# Main.net
KiCad netlist of a schematic drawn in EAGLE
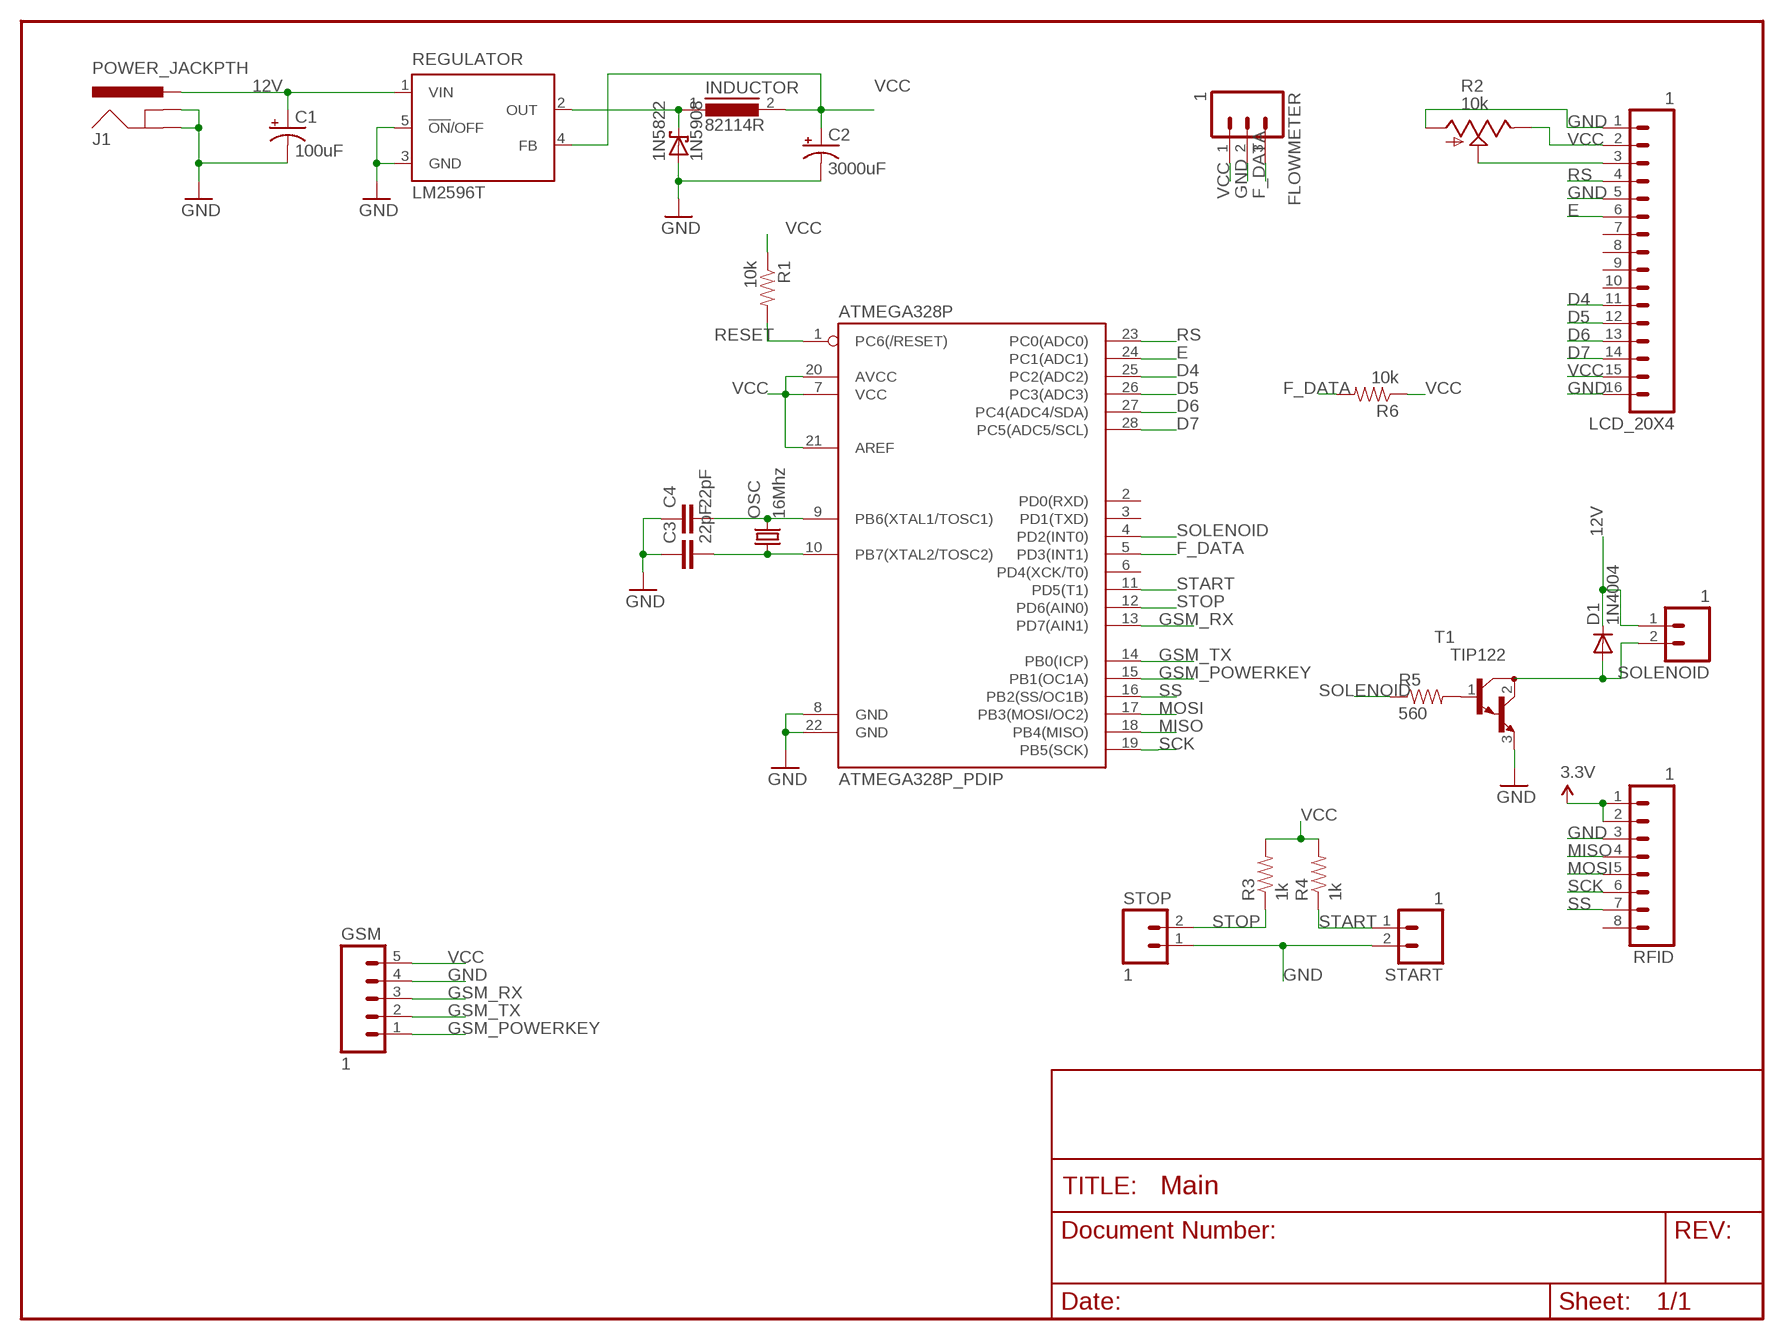
[diagram p0: schematic, sheet 1]

(export (version "E")
  (design (tool "Eeschema 10.0.6"))
  (components
    (comp (ref "1N5822")
      (value "1N5908")
      (footprint "eagle-import:C4111-15")
      (libsource (lib "eagle-import") (part "1N5908"))
    )
    (comp (ref "ATMEGA328P")
      (value "ATMEGA328P_PDIP")
      (footprint "eagle-import:DIL28-3")
      (libsource (lib "eagle-import") (part "ATMEGA328P_PDIP"))
    )
    (comp (ref "C1")
      (value "100uF")
      (footprint "eagle-import:CPOL-RADIAL-10UF-25V")
      (libsource (lib "eagle-import") (part "CAP_POLPTH2"))
    )
    (comp (ref "C2")
      (value "3000uF")
      (footprint "eagle-import:CPOL-RADIAL-1000UF-25V")
      (libsource (lib "eagle-import") (part "CAP_POLPTH4"))
    )
    (comp (ref "C3")
      (value "22pF")
      (footprint "eagle-import:CAP-PTH-SMALL")
      (libsource (lib "eagle-import") (part "CAPPTH"))
    )
    (comp (ref "C4")
      (value "22pF")
      (footprint "eagle-import:CAP-PTH-SMALL")
      (libsource (lib "eagle-import") (part "CAPPTH"))
    )
    (comp (ref "D1")
      (value "1N4004")
      (footprint "eagle-import:DO41-10")
      (libsource (lib "eagle-import") (part "1N4004"))
    )
    (comp (ref "FLOWMETER")
      (value "1")
      (footprint "eagle-import:1X03")
      (libsource (lib "eagle-import") (part "M03PTH"))
    )
    (comp (ref "GSM")
      (value "1")
      (footprint "eagle-import:1X05_LONGPADS")
      (libsource (lib "eagle-import") (part "M05PTH_LONGPADS"))
    )
    (comp (ref "INDUCTOR")
      (value "82114R")
      (footprint "eagle-import:82114R")
      (libsource (lib "eagle-import") (part "82114R"))
    )
    (comp (ref "J1")
      (value "POWER_JACKPTH")
      (footprint "eagle-import:POWER_JACK_PTH")
      (libsource (lib "eagle-import") (part "POWER_JACKPTH"))
    )
    (comp (ref "LCD_20X4")
      (value "1")
      (footprint "eagle-import:1X16")
      (libsource (lib "eagle-import") (part "M16PTH"))
    )
    (comp (ref "OSC")
      (value "16Mhz")
      (footprint "eagle-import:HC49US")
      (libsource (lib "eagle-import") (part "CRYSTALHC49US"))
    )
    (comp (ref "R1")
      (value "10k")
      (footprint "eagle-import:AXIAL-0.4")
      (libsource (lib "eagle-import") (part "SparkFun-Passives_RESISTORPTH-1/4W"))
    )
    (comp (ref "R2")
      (value "10k")
      (footprint "eagle-import:CA6V")
      (libsource (lib "eagle-import") (part "TRIM_US-CA6V"))
    )
    (comp (ref "R3")
      (value "1k")
      (footprint "eagle-import:AXIAL-0.4")
      (libsource (lib "eagle-import") (part "RESISTORPTH-1/4W"))
    )
    (comp (ref "R4")
      (value "1k")
      (footprint "eagle-import:AXIAL-0.4")
      (libsource (lib "eagle-import") (part "RESISTORPTH-1/4W"))
    )
    (comp (ref "R5")
      (value "560")
      (footprint "eagle-import:AXIAL-0.5")
      (libsource (lib "eagle-import") (part "RESISTORPTH-1/2W"))
    )
    (comp (ref "R6")
      (value "10k")
      (footprint "eagle-import:AXIAL-0.4")
      (libsource (lib "eagle-import") (part "SparkFun-Passives_RESISTORPTH-1/4W"))
    )
    (comp (ref "REGULATOR")
      (value "LM2596T")
      (footprint "eagle-import:T05D")
      (fields (field (name "MPN") "LM2596T-ADJ/LF02"))
      (libsource (lib "eagle-import") (part "LM2596T"))
    )
    (comp (ref "RFID")
      (value "1")
      (footprint "eagle-import:1X08_ROUND")
      (libsource (lib "eagle-import") (part "M08"))
    )
    (comp (ref "SOLENOID")
      (value "1")
      (footprint "eagle-import:1X02")
      (libsource (lib "eagle-import") (part "M02PTH"))
    )
    (comp (ref "START")
      (value "1")
      (footprint "eagle-import:1X02")
      (libsource (lib "eagle-import") (part "M02PTH"))
    )
    (comp (ref "STOP")
      (value "1")
      (footprint "eagle-import:1X02")
      (libsource (lib "eagle-import") (part "M02PTH"))
    )
    (comp (ref "T1")
      (value "TIP122")
      (footprint "eagle-import:TO220")
      (libsource (lib "eagle-import") (part "TIP122"))
    )
  )
  (nets
    (net (code "1") (name "/12V") (class "Default")
      (node (ref "C1") (pin "1") (pinfunction "+_1") (pintype "passive"))
      (node (ref "D1") (pin "C") (pinfunction "C_C") (pintype "passive"))
      (node (ref "J1") (pin "PWR") (pinfunction "PWR_PWR") (pintype "bidirectional"))
      (node (ref "REGULATOR") (pin "1") (pinfunction "VIN_1") (pintype "input"))
      (node (ref "SOLENOID") (pin "1") (pinfunction "1_1") (pintype "passive"))
    )
    (net (code "2") (name "/D4") (class "Default")
      (node (ref "ATMEGA328P") (pin "25") (pinfunction "PC2(ADC2)_25") (pintype "bidirectional"))
      (node (ref "LCD_20X4") (pin "11") (pinfunction "11_11") (pintype "passive"))
    )
    (net (code "3") (name "/D5") (class "Default")
      (node (ref "ATMEGA328P") (pin "26") (pinfunction "PC3(ADC3)_26") (pintype "bidirectional"))
      (node (ref "LCD_20X4") (pin "12") (pinfunction "12_12") (pintype "passive"))
    )
    (net (code "4") (name "/D6") (class "Default")
      (node (ref "ATMEGA328P") (pin "27") (pinfunction "PC4(ADC4/SDA)_27") (pintype "bidirectional"))
      (node (ref "LCD_20X4") (pin "13") (pinfunction "13_13") (pintype "passive"))
    )
    (net (code "5") (name "/D7") (class "Default")
      (node (ref "ATMEGA328P") (pin "28") (pinfunction "PC5(ADC5/SCL)_28") (pintype "bidirectional"))
      (node (ref "LCD_20X4") (pin "14") (pinfunction "14_14") (pintype "passive"))
    )
    (net (code "6") (name "/E") (class "Default")
      (node (ref "ATMEGA328P") (pin "24") (pinfunction "PC1(ADC1)_24") (pintype "bidirectional"))
      (node (ref "LCD_20X4") (pin "6") (pinfunction "6_6") (pintype "passive"))
    )
    (net (code "7") (name "/F_DATA") (class "Default")
      (node (ref "ATMEGA328P") (pin "5") (pinfunction "PD3(INT1)_5") (pintype "bidirectional"))
      (node (ref "FLOWMETER") (pin "3") (pinfunction "3_3") (pintype "passive"))
      (node (ref "R6") (pin "P$2") (pinfunction "2_P$2") (pintype "passive"))
    )
    (net (code "8") (name "/GSM_POWERKEY") (class "Default")
      (node (ref "ATMEGA328P") (pin "15") (pinfunction "PB1(OC1A)_15") (pintype "bidirectional"))
      (node (ref "GSM") (pin "1") (pinfunction "1_1") (pintype "passive"))
    )
    (net (code "9") (name "/GSM_RX") (class "Default")
      (node (ref "ATMEGA328P") (pin "13") (pinfunction "PD7(AIN1)_13") (pintype "bidirectional"))
      (node (ref "GSM") (pin "3") (pinfunction "3_3") (pintype "passive"))
    )
    (net (code "10") (name "/GSM_TX") (class "Default")
      (node (ref "ATMEGA328P") (pin "14") (pinfunction "PB0(ICP)_14") (pintype "bidirectional"))
      (node (ref "GSM") (pin "2") (pinfunction "2_2") (pintype "passive"))
    )
    (net (code "11") (name "/MISO") (class "Default")
      (node (ref "ATMEGA328P") (pin "18") (pinfunction "PB4(MISO)_18") (pintype "bidirectional"))
      (node (ref "RFID") (pin "4") (pinfunction "4_4") (pintype "passive"))
    )
    (net (code "12") (name "/MOSI") (class "Default")
      (node (ref "ATMEGA328P") (pin "17") (pinfunction "PB3(MOSI/OC2)_17") (pintype "bidirectional"))
      (node (ref "RFID") (pin "5") (pinfunction "5_5") (pintype "passive"))
    )
    (net (code "13") (name "/RESET") (class "Default")
      (node (ref "ATMEGA328P") (pin "1") (pinfunction "PC6(/RESET)_1") (pintype "bidirectional"))
      (node (ref "R1") (pin "P$2") (pinfunction "2_P$2") (pintype "passive"))
    )
    (net (code "14") (name "/RS") (class "Default")
      (node (ref "ATMEGA328P") (pin "23") (pinfunction "PC0(ADC0)_23") (pintype "bidirectional"))
      (node (ref "LCD_20X4") (pin "4") (pinfunction "4_4") (pintype "passive"))
    )
    (net (code "15") (name "/SCK") (class "Default")
      (node (ref "ATMEGA328P") (pin "19") (pinfunction "PB5(SCK)_19") (pintype "bidirectional"))
      (node (ref "RFID") (pin "6") (pinfunction "6_6") (pintype "passive"))
    )
    (net (code "16") (name "/SOLENOID") (class "Default")
      (node (ref "ATMEGA328P") (pin "4") (pinfunction "PD2(INT0)_4") (pintype "bidirectional"))
      (node (ref "R5") (pin "P$1") (pinfunction "1_P$1") (pintype "passive"))
    )
    (net (code "17") (name "/SS") (class "Default")
      (node (ref "ATMEGA328P") (pin "16") (pinfunction "PB2(SS/OC1B)_16") (pintype "bidirectional"))
      (node (ref "RFID") (pin "7") (pinfunction "7_7") (pintype "passive"))
    )
    (net (code "18") (name "/START") (class "Default")
      (node (ref "ATMEGA328P") (pin "11") (pinfunction "PD5(T1)_11") (pintype "bidirectional"))
      (node (ref "R4") (pin "P$1") (pinfunction "1_P$1") (pintype "passive"))
      (node (ref "START") (pin "1") (pinfunction "1_1") (pintype "passive"))
    )
    (net (code "19") (name "/STOP") (class "Default")
      (node (ref "ATMEGA328P") (pin "12") (pinfunction "PD6(AIN0)_12") (pintype "bidirectional"))
      (node (ref "R3") (pin "P$1") (pinfunction "1_P$1") (pintype "passive"))
      (node (ref "STOP") (pin "2") (pinfunction "2_2") (pintype "passive"))
    )
    (net (code "20") (name "/VCC") (class "Default")
      (node (ref "ATMEGA328P") (pin "20") (pinfunction "AVCC_20") (pintype "bidirectional"))
      (node (ref "ATMEGA328P") (pin "21") (pinfunction "AREF_21") (pintype "bidirectional"))
      (node (ref "ATMEGA328P") (pin "7") (pinfunction "VCC_7") (pintype "bidirectional"))
      (node (ref "C2") (pin "1") (pinfunction "+_1") (pintype "passive"))
      (node (ref "FLOWMETER") (pin "1") (pinfunction "1_1") (pintype "passive"))
      (node (ref "GSM") (pin "5") (pinfunction "5_5") (pintype "passive"))
      (node (ref "INDUCTOR") (pin "2") (pinfunction "2_2") (pintype "passive"))
      (node (ref "LCD_20X4") (pin "15") (pinfunction "15_15") (pintype "passive"))
      (node (ref "LCD_20X4") (pin "2") (pinfunction "2_2") (pintype "passive"))
      (node (ref "R1") (pin "P$1") (pinfunction "1_P$1") (pintype "passive"))
      (node (ref "R2") (pin "E") (pinfunction "E_E") (pintype "passive"))
      (node (ref "R3") (pin "P$2") (pinfunction "2_P$2") (pintype "passive"))
      (node (ref "R4") (pin "P$2") (pinfunction "2_P$2") (pintype "passive"))
      (node (ref "R6") (pin "P$1") (pinfunction "1_P$1") (pintype "passive"))
      (node (ref "REGULATOR") (pin "4") (pinfunction "FB_4") (pintype "input"))
    )
    (net (code "21") (name "3.3V") (class "Default")
      (node (ref "RFID") (pin "1") (pinfunction "1_1") (pintype "passive"))
      (node (ref "RFID") (pin "2") (pinfunction "2_2") (pintype "passive"))
    )
    (net (code "22") (name "GND") (class "Default")
      (node (ref "1N5822") (pin "A") (pinfunction "A_A") (pintype "passive"))
      (node (ref "ATMEGA328P") (pin "22") (pinfunction "GND_22") (pintype "bidirectional"))
      (node (ref "ATMEGA328P") (pin "8") (pinfunction "GND_8") (pintype "bidirectional"))
      (node (ref "C1") (pin "2") (pinfunction "-_2") (pintype "passive"))
      (node (ref "C2") (pin "2") (pinfunction "-_2") (pintype "passive"))
      (node (ref "C3") (pin "1") (pinfunction "1_1") (pintype "passive"))
      (node (ref "C4") (pin "1") (pinfunction "1_1") (pintype "passive"))
      (node (ref "FLOWMETER") (pin "2") (pinfunction "2_2") (pintype "passive"))
      (node (ref "GSM") (pin "4") (pinfunction "4_4") (pintype "passive"))
      (node (ref "J1") (pin "GND") (pinfunction "GND_GND") (pintype "bidirectional"))
      (node (ref "J1") (pin "GNDBREAK") (pinfunction "GNDBREAK_GNDBREAK") (pintype "bidirectional"))
      (node (ref "LCD_20X4") (pin "1") (pinfunction "1_1") (pintype "passive"))
      (node (ref "LCD_20X4") (pin "16") (pinfunction "16_16") (pintype "passive"))
      (node (ref "LCD_20X4") (pin "5") (pinfunction "5_5") (pintype "passive"))
      (node (ref "R2") (pin "A") (pinfunction "A_A") (pintype "passive"))
      (node (ref "REGULATOR") (pin "3") (pinfunction "GND_3") (pintype "power_in"))
      (node (ref "REGULATOR") (pin "5") (pinfunction "~{ON}/OFF_5") (pintype "input"))
      (node (ref "RFID") (pin "3") (pinfunction "3_3") (pintype "passive"))
      (node (ref "START") (pin "2") (pinfunction "2_2") (pintype "passive"))
      (node (ref "STOP") (pin "1") (pinfunction "1_1") (pintype "passive"))
      (node (ref "T1") (pin "3") (pinfunction "E_3") (pintype "passive"))
    )
    (net (code "23") (name "Net-(ATMEGA328P-PB6(XTAL1{slash}TOSC1))") (class "Default")
      (node (ref "ATMEGA328P") (pin "9") (pinfunction "PB6(XTAL1/TOSC1)_9") (pintype "bidirectional"))
      (node (ref "C4") (pin "2") (pinfunction "2_2") (pintype "passive"))
      (node (ref "OSC") (pin "2") (pinfunction "2_2") (pintype "passive"))
    )
    (net (code "24") (name "Net-(ATMEGA328P-PB7(XTAL2{slash}TOSC2))") (class "Default")
      (node (ref "ATMEGA328P") (pin "10") (pinfunction "PB7(XTAL2/TOSC2)_10") (pintype "bidirectional"))
      (node (ref "C3") (pin "2") (pinfunction "2_2") (pintype "passive"))
      (node (ref "OSC") (pin "1") (pinfunction "1_1") (pintype "passive"))
    )
    (net (code "25") (name "Net-(LCD_20X4-Pad3)") (class "Default")
      (node (ref "LCD_20X4") (pin "3") (pinfunction "3_3") (pintype "passive"))
      (node (ref "R2") (pin "S") (pinfunction "S_S") (pintype "passive"))
    )
    (net (code "26") (name "Net-(R5-2)") (class "Default")
      (node (ref "R5") (pin "P$2") (pinfunction "2_P$2") (pintype "passive"))
      (node (ref "T1") (pin "1") (pinfunction "B_1") (pintype "passive"))
    )
    (net (code "27") (name "Net-(REGULATOR-OUT)") (class "Default")
      (node (ref "1N5822") (pin "C") (pinfunction "C_C") (pintype "passive"))
      (node (ref "INDUCTOR") (pin "1") (pinfunction "1_1") (pintype "passive"))
      (node (ref "REGULATOR") (pin "2") (pinfunction "OUT_2") (pintype "output"))
    )
    (net (code "28") (name "Net-(T1-C)") (class "Default")
      (node (ref "D1") (pin "A") (pinfunction "A_A") (pintype "passive"))
      (node (ref "SOLENOID") (pin "2") (pinfunction "2_2") (pintype "passive"))
      (node (ref "T1") (pin "2") (pinfunction "C_2") (pintype "passive"))
    )
    (net (code "29") (name "unconnected-(ATMEGA328P-PD0(RXD)-Pad2)") (class "Default")
      (node (ref "ATMEGA328P") (pin "2") (pinfunction "PD0(RXD)_2") (pintype "bidirectional"))
    )
    (net (code "30") (name "unconnected-(ATMEGA328P-PD1(TXD)-Pad3)") (class "Default")
      (node (ref "ATMEGA328P") (pin "3") (pinfunction "PD1(TXD)_3") (pintype "bidirectional"))
    )
    (net (code "31") (name "unconnected-(ATMEGA328P-PD4(XCK{slash}T0)-Pad6)") (class "Default")
      (node (ref "ATMEGA328P") (pin "6") (pinfunction "PD4(XCK/T0)_6") (pintype "bidirectional"))
    )
    (net (code "32") (name "unconnected-(LCD_20X4-Pad7)") (class "Default")
      (node (ref "LCD_20X4") (pin "7") (pinfunction "7_7") (pintype "passive"))
    )
    (net (code "33") (name "unconnected-(LCD_20X4-Pad8)") (class "Default")
      (node (ref "LCD_20X4") (pin "8") (pinfunction "8_8") (pintype "passive"))
    )
    (net (code "34") (name "unconnected-(LCD_20X4-Pad9)") (class "Default")
      (node (ref "LCD_20X4") (pin "9") (pinfunction "9_9") (pintype "passive"))
    )
    (net (code "35") (name "unconnected-(LCD_20X4-Pad10)") (class "Default")
      (node (ref "LCD_20X4") (pin "10") (pinfunction "10_10") (pintype "passive"))
    )
    (net (code "36") (name "unconnected-(RFID-Pad8)") (class "Default")
      (node (ref "RFID") (pin "8") (pinfunction "8_8") (pintype "passive"))
    )
  )
)
